# IR_CONTROLLER.net
KiCad netlist of a schematic drawn in Altium Designer
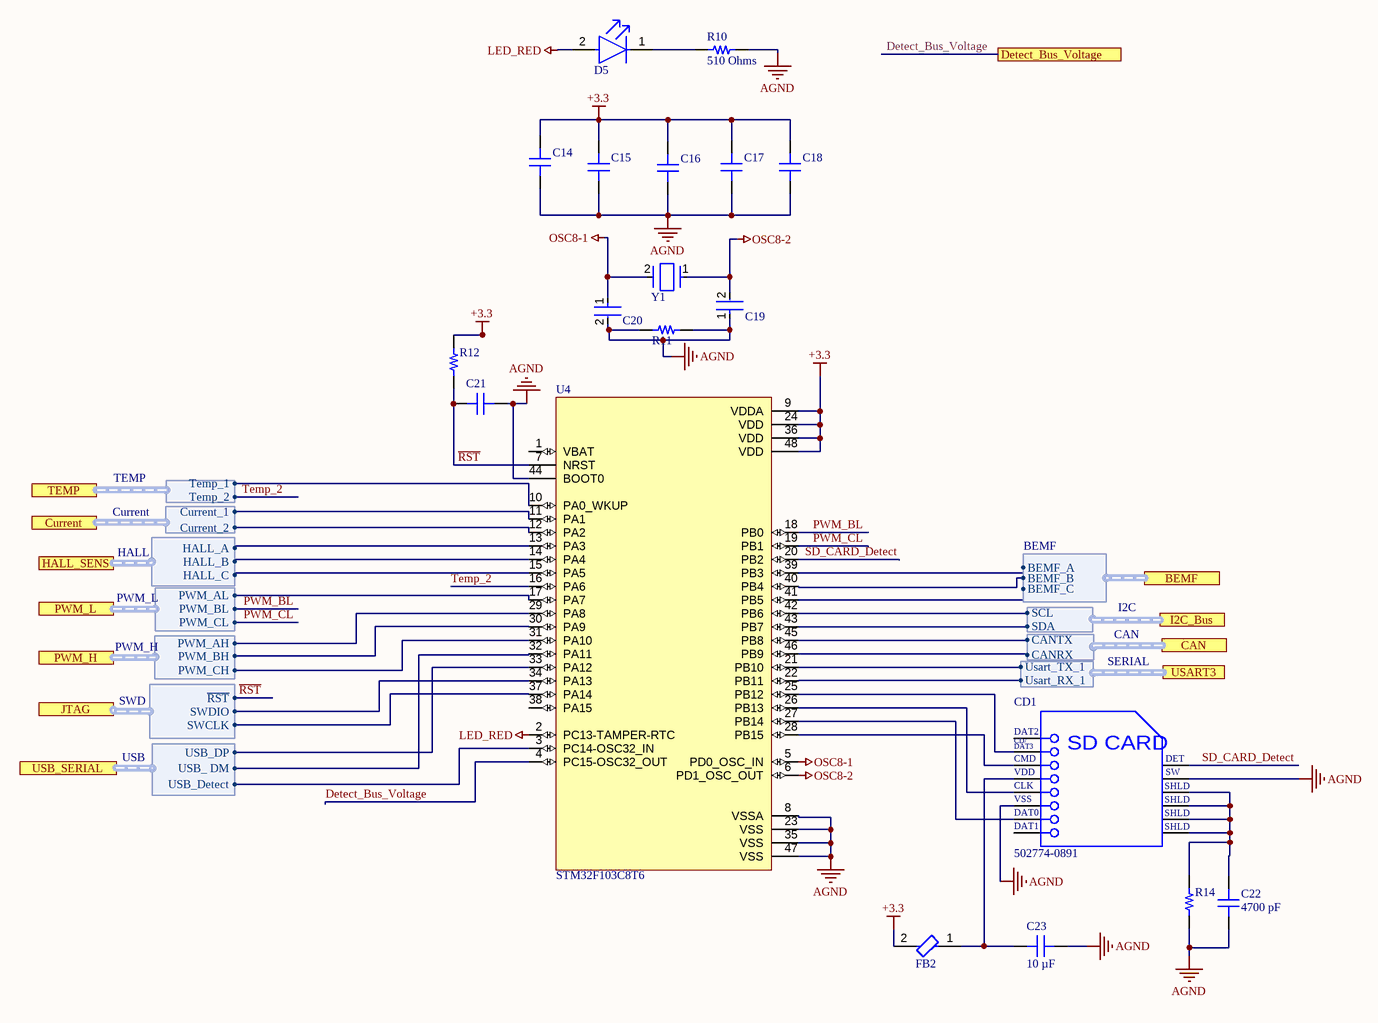
[diagram p0: IR_CONTROLLER.SchDoc]

(export (version "E")
  (design (tool "Eeschema 10.0.6"))
  (components
    (comp (ref "C14")
      (value "0.1 µF")
      (footprint "CAP 0603_1608")
      (description "CAP CER 0.1UF 16V X7R 0603")
      (fields (field (name "PART NUMBER") "CS0603KRX7R7BB104"))
      (libsource (lib "Celestial Altium Library - altium_library") (part "Capacitor"))
    )
    (comp (ref "C15")
      (value "0.1 µF")
      (footprint "CAP 0603_1608")
      (description "CAP CER 0.1UF 16V X7R 0603")
      (fields (field (name "PART NUMBER") "CS0603KRX7R7BB104"))
      (libsource (lib "Celestial Altium Library - altium_library") (part "Capacitor"))
    )
    (comp (ref "C16")
      (value "0.1 µF")
      (footprint "CAP 0603_1608")
      (description "CAP CER 0.1UF 16V X7R 0603")
      (fields (field (name "PART NUMBER") "CS0603KRX7R7BB104"))
      (libsource (lib "Celestial Altium Library - altium_library") (part "Capacitor"))
    )
    (comp (ref "C17")
      (value "0.1 µF")
      (footprint "CAP 0603_1608")
      (description "CAP CER 0.1UF 16V X7R 0603")
      (fields (field (name "PART NUMBER") "CS0603KRX7R7BB104"))
      (libsource (lib "Celestial Altium Library - altium_library") (part "Capacitor"))
    )
    (comp (ref "C18")
      (value "10 µF")
      (footprint "CAP 0603_1608")
      (description "CAP CER 10UF 2.5V X6S 0603")
      (fields (field (name "PART NUMBER") "GRM188C80E106ME47D"))
      (libsource (lib "Celestial Altium Library - altium_library") (part "Capacitor"))
    )
    (comp (ref "C19")
      (value "10pF")
      (footprint "FP-C0805C-DN-MFG")
      (description "Capacitor; Ceramic; Cap 10 pF; Tol 5%; Vol-Rtg 50 VDC; SMT; 0805; COG (NPO); Tape&Reel")
      (fields
        (field (name "OCTOPART") "https://octopart.com/c0805c100j5gactu-kemet-104357")
        (field (name "MANUFACTURER PART NUMBER") "C0805C100J5GACTU")
      )
      (libsource (lib "Altium Content Vault") (part "b4654b650e69147ec39a6b967a45e02"))
    )
    (comp (ref "C20")
      (value "10pF")
      (footprint "FP-C0805C-DN-MFG")
      (description "Capacitor; Ceramic; Cap 10 pF; Tol 5%; Vol-Rtg 50 VDC; SMT; 0805; COG (NPO); Tape&Reel")
      (fields
        (field (name "OCTOPART") "https://octopart.com/c0805c100j5gactu-kemet-104357")
        (field (name "MANUFACTURER PART NUMBER") "C0805C100J5GACTU")
      )
      (libsource (lib "Altium Content Vault") (part "b4654b650e69147ec39a6b967a45e02"))
    )
    (comp (ref "C21")
      (value "100 nF")
      (footprint "CAP 0603_1608")
      (description "CAP CER 10UF 2.5V X6S 0603")
      (fields (field (name "PART NUMBER") "GRM188C80E106ME47D"))
      (libsource (lib "Celestial Altium Library - altium_library") (part "Capacitor"))
    )
    (comp (ref "C22")
      (value "4700 pF")
      (footprint "CAP 0805_2012")
      (description "CAP CER 4700PF 50V X7R 0805")
      (fields (field (name "PART NUMBER") "C0805C472K5RACAUTO") (field (name "MANUFACTURER") "KEMET"))
      (libsource (lib "Celestial Altium Library - altium_library") (part "Capacitor"))
    )
    (comp (ref "C23")
      (value "10 µF")
      (footprint "CAP 0603_1608")
      (description "CAP CER 10UF 6.3V X5R 0603")
      (fields
        (field (name "PART NUMBER") "GRM188R60J106ME47D")
        (field (name "MANUFACTURER") "Murata Electronics")
      )
      (libsource (lib "Celestial Altium Library - altium_library") (part "Capacitor"))
    )
    (comp (ref "CD1")
      (value "502774-0891")
      (footprint "MOLX-502774-0891_V")
      (description "Micro SD Memory Card Connector, 0.5 A, 10 V (DC), -25 to 85 degC, 8-Pin SMT, RoHS, Tape and Reel")
      (fields (field (name "MANUFACTURER") "Molex"))
      (libsource (lib "Altium Content Vault") (part "CN-SD-8-2SW-4S_B"))
    )
    (comp (ref "D5")
      (value "CMD15-21VRD/TR8")
      (footprint "FP-CMD15-21-MFG")
      (description "LED RED DIFFUSED 1206 SMD")
      (fields
        (field (name "MANUFACTURER") "VCC")
        (field (name "OCTOPART") "https://octopart.com/cmd15-21vrd%2Ftr8-vcc-26668835")
      )
      (libsource (lib "Altium Content Vault") (part "8706943c75ba83719d021d2fdc84c58"))
    )
    (comp (ref "FB2")
      (value "BLM18PG330SN1D")
      (footprint "FP-BLM18-0_15-t0_8-d1_2-MFG")
      (description "Chip Ferrite Bead, 0603, 33Ω @ 100MHz, 0.025Ω, 25%, 3A")
      (fields (field (name "TOLERANCE") "25%"))
      (libsource (lib "Altium Content Vault") (part "5f30dd21d616792df468990f7003faa"))
    )
    (comp (ref "R10")
      (value "510 Ohms")
      (footprint "RES 0603_1608")
      (description "RES 10K OHM 0.1% 1/16W 0603")
      (fields
        (field (name "PART NUMBER") "RNCS0603BKE10K0")
        (field (name "MANUFACTURER") "Stackpole Electronics Inc")
      )
      (libsource (lib "Celestial Altium Library - altium_library") (part "Resistor"))
    )
    (comp (ref "R11")
      (value "1M Ohms")
      (footprint "RES 0603_1608")
      (description "RES 10K OHM 0.1% 1/16W 0603")
      (fields
        (field (name "PART NUMBER") "RNCS0603BKE10K0")
        (field (name "MANUFACTURER") "Stackpole Electronics Inc")
      )
      (libsource (lib "Celestial Altium Library - altium_library") (part "Resistor"))
    )
    (comp (ref "R12")
      (value "4.7 kOhms")
      (footprint "RES 0603_1608")
      (description "RES SMD 4.7K OHM 0.1% 1/16W 0603")
      (fields
        (field (name "PART NUMBER") "CPF0603B4K7E1")
        (field (name "MANUFACTURER") "TE Connectivity Passive Product")
      )
      (libsource (lib "Celestial Altium Library - altium_library") (part "Resistor"))
    )
    (comp (ref "R14")
      (value "1 MOhms")
      (footprint "RES 0603_1608")
      (description "RES SMD 1M OHM 0.1% 1/10W 0603")
      (fields (field (name "PART NUMBER") "RT0603BRD071ML") (field (name "MANUFACTURER") "Yageo"))
      (libsource (lib "Celestial Altium Library - altium_library") (part "Resistor"))
    )
    (comp (ref "U4")
      (value "STM32F103C8T6")
      (footprint "QFN48-(7mmX7mm)")
      (description "IC MCU 32-Bit 72MHz 64kB FLASH LQFP48")
      (fields (field (name "MF") "STMicroelectronics"))
      (libsource (lib "Altium_Lib") (part "STM32F103C8T6"))
    )
    (comp (ref "Y1")
      (value "ABM3-8.000MHZ-D2Y-T")
      (footprint "FP-ABM3-MFG")
      (description "Crystal 8MHz ±20ppm 18pF SMD-2 5mm x 3.2mm")
      (fields (field (name "TOLERANCE") "20ppm"))
      (libsource (lib "Altium Content Vault") (part "c23a69dc6c9e2f18f2079038eb95dd1"))
    )
  )
  (nets
    (net (code "12") (name "+3.3") (class "Default")
      (node (ref "C14") (pin "2") (pinfunction "2_2") (pintype "passive"))
      (node (ref "C15") (pin "2") (pinfunction "2_2") (pintype "passive"))
      (node (ref "C16") (pin "2") (pinfunction "2_2") (pintype "passive"))
      (node (ref "C17") (pin "2") (pinfunction "2_2") (pintype "passive"))
      (node (ref "C18") (pin "2") (pinfunction "2_2") (pintype "passive"))
      (node (ref "FB2") (pin "2") (pinfunction "2_2") (pintype "passive"))
      (node (ref "R12") (pin "2") (pinfunction "2_2") (pintype "passive"))
      (node (ref "U4") (pin "24") (pinfunction "VDD_24") (pintype "passive"))
      (node (ref "U4") (pin "36") (pinfunction "VDD_36") (pintype "passive"))
      (node (ref "U4") (pin "48") (pinfunction "VDD_48") (pintype "passive"))
      (node (ref "U4") (pin "9") (pinfunction "VDDA_9") (pintype "passive"))
    )
    (net (code "13") (name "/BEMF_A") (class "Default")
      (node (ref "U4") (pin "39") (pinfunction "PB3_39") (pintype "bidirectional"))
    )
    (net (code "14") (name "/BEMF_B") (class "Default")
      (node (ref "U4") (pin "40") (pinfunction "PB4_40") (pintype "bidirectional"))
    )
    (net (code "15") (name "/BEMF_C") (class "Default")
      (node (ref "U4") (pin "41") (pinfunction "PB5_41") (pintype "bidirectional"))
    )
    (net (code "16") (name "/CANRX") (class "Default")
      (node (ref "U4") (pin "46") (pinfunction "PB9_46") (pintype "bidirectional"))
    )
    (net (code "17") (name "/CANTX") (class "Default")
      (node (ref "U4") (pin "45") (pinfunction "PB8_45") (pintype "bidirectional"))
    )
    (net (code "18") (name "/Current_1") (class "Default")
      (node (ref "U4") (pin "11") (pinfunction "PA1_11") (pintype "bidirectional"))
    )
    (net (code "19") (name "/Current_2") (class "Default")
      (node (ref "U4") (pin "12") (pinfunction "PA2_12") (pintype "bidirectional"))
    )
    (net (code "20") (name "/Detect_Bus_Voltage") (class "Default")
      (node (ref "U4") (pin "4") (pinfunction "PC15-OSC32_OUT_4") (pintype "bidirectional"))
    )
    (net (code "21") (name "/HALL_A") (class "Default")
      (node (ref "U4") (pin "13") (pinfunction "PA3_13") (pintype "bidirectional"))
    )
    (net (code "22") (name "/HALL_B") (class "Default")
      (node (ref "U4") (pin "14") (pinfunction "PA4_14") (pintype "bidirectional"))
    )
    (net (code "23") (name "/HALL_C") (class "Default")
      (node (ref "U4") (pin "15") (pinfunction "PA5_15") (pintype "bidirectional"))
    )
    (net (code "24") (name "/PWM_AH") (class "Default")
      (node (ref "U4") (pin "29") (pinfunction "PA8_29") (pintype "bidirectional"))
    )
    (net (code "25") (name "/PWM_AL") (class "Default")
      (node (ref "U4") (pin "17") (pinfunction "PA7_17") (pintype "bidirectional"))
    )
    (net (code "26") (name "/PWM_BH") (class "Default")
      (node (ref "U4") (pin "30") (pinfunction "PA9_30") (pintype "bidirectional"))
    )
    (net (code "27") (name "/PWM_BL") (class "Default")
      (node (ref "U4") (pin "18") (pinfunction "PB0_18") (pintype "bidirectional"))
    )
    (net (code "28") (name "/PWM_CH") (class "Default")
      (node (ref "U4") (pin "31") (pinfunction "PA10_31") (pintype "bidirectional"))
    )
    (net (code "29") (name "/PWM_CL") (class "Default")
      (node (ref "U4") (pin "19") (pinfunction "PB1_19") (pintype "bidirectional"))
    )
    (net (code "31") (name "/SCL") (class "Default")
      (node (ref "U4") (pin "42") (pinfunction "PB6_42") (pintype "bidirectional"))
    )
    (net (code "32") (name "/SDA") (class "Default")
      (node (ref "U4") (pin "43") (pinfunction "PB7_43") (pintype "bidirectional"))
    )
    (net (code "33") (name "/SD_CARD_Detect") (class "Default")
      (node (ref "CD1") (pin "9") (pinfunction "DETECT_9") (pintype "passive"))
      (node (ref "U4") (pin "20") (pinfunction "PB2_20") (pintype "bidirectional"))
    )
    (net (code "34") (name "/SWCLK") (class "Default")
      (node (ref "U4") (pin "37") (pinfunction "PA14_37") (pintype "bidirectional"))
    )
    (net (code "35") (name "/SWDIO") (class "Default")
      (node (ref "U4") (pin "34") (pinfunction "PA13_34") (pintype "bidirectional"))
    )
    (net (code "36") (name "/Temp_1") (class "Default")
      (node (ref "U4") (pin "10") (pinfunction "PA0_WKUP_10") (pintype "bidirectional"))
    )
    (net (code "37") (name "/Temp_2") (class "Default")
      (node (ref "U4") (pin "16") (pinfunction "PA6_16") (pintype "bidirectional"))
    )
    (net (code "38") (name "/USB_ DM") (class "Default")
      (node (ref "U4") (pin "32") (pinfunction "PA11_32") (pintype "bidirectional"))
    )
    (net (code "39") (name "/USB_DP") (class "Default")
      (node (ref "U4") (pin "33") (pinfunction "PA12_33") (pintype "bidirectional"))
    )
    (net (code "40") (name "/USB_Detect") (class "Default")
      (node (ref "U4") (pin "3") (pinfunction "PC14-OSC32_IN_3") (pintype "bidirectional"))
    )
    (net (code "41") (name "/Usart_RX_1") (class "Default")
      (node (ref "U4") (pin "22") (pinfunction "PB11_22") (pintype "bidirectional"))
    )
    (net (code "42") (name "/Usart_TX_1") (class "Default")
      (node (ref "U4") (pin "21") (pinfunction "PB10_21") (pintype "bidirectional"))
    )
    (net (code "53") (name "/~{RST}") (class "Default")
      (node (ref "C21") (pin "2") (pinfunction "2_2") (pintype "passive"))
      (node (ref "R12") (pin "1") (pinfunction "1_1") (pintype "passive"))
      (node (ref "U4") (pin "7") (pinfunction "NRST_7") (pintype "passive"))
    )
    (net (code "54") (name "AGND") (class "Default")
      (node (ref "C14") (pin "1") (pinfunction "1_1") (pintype "passive"))
      (node (ref "C15") (pin "1") (pinfunction "1_1") (pintype "passive"))
      (node (ref "C16") (pin "1") (pinfunction "1_1") (pintype "passive"))
      (node (ref "C17") (pin "1") (pinfunction "1_1") (pintype "passive"))
      (node (ref "C18") (pin "1") (pinfunction "1_1") (pintype "passive"))
      (node (ref "C19") (pin "1") (pinfunction "1_1") (pintype "passive"))
      (node (ref "C20") (pin "2") (pinfunction "2_2") (pintype "passive"))
      (node (ref "C21") (pin "1") (pinfunction "1_1") (pintype "passive"))
      (node (ref "C22") (pin "1") (pinfunction "1_1") (pintype "passive"))
      (node (ref "C23") (pin "2") (pinfunction "2_2") (pintype "passive"))
      (node (ref "CD1") (pin "10") (pinfunction "SWITCH_10") (pintype "passive"))
      (node (ref "CD1") (pin "6") (pinfunction "VSS_6") (pintype "passive"))
      (node (ref "R10") (pin "2") (pinfunction "2_2") (pintype "passive"))
      (node (ref "R11") (pin "1") (pinfunction "1_1") (pintype "passive"))
      (node (ref "R11") (pin "2") (pinfunction "2_2") (pintype "passive"))
      (node (ref "R14") (pin "1") (pinfunction "1_1") (pintype "passive"))
      (node (ref "U4") (pin "23") (pinfunction "VSS_23") (pintype "passive"))
      (node (ref "U4") (pin "35") (pinfunction "VSS_35") (pintype "passive"))
      (node (ref "U4") (pin "44") (pinfunction "BOOT0_44") (pintype "passive"))
      (node (ref "U4") (pin "47") (pinfunction "VSS_47") (pintype "passive"))
      (node (ref "U4") (pin "8") (pinfunction "VSSA_8") (pintype "passive"))
    )
    (net (code "55") (name "LED_RED") (class "Default")
      (node (ref "D5") (pin "2") (pinfunction "A_2") (pintype "passive"))
      (node (ref "U4") (pin "2") (pinfunction "PC13-TAMPER-RTC_2") (pintype "bidirectional"))
    )
    (net (code "56") (name "Net-(C22-Pad2)") (class "Default")
      (node (ref "C22") (pin "2") (pinfunction "2_2") (pintype "passive"))
      (node (ref "CD1") (pin "11") (pinfunction "SHLD_11") (pintype "passive"))
      (node (ref "CD1") (pin "12") (pinfunction "SHLD_12") (pintype "passive"))
      (node (ref "CD1") (pin "13") (pinfunction "SHLD_13") (pintype "passive"))
      (node (ref "CD1") (pin "14") (pinfunction "SHLD_14") (pintype "passive"))
      (node (ref "R14") (pin "2") (pinfunction "2_2") (pintype "passive"))
    )
    (net (code "57") (name "Net-(CD1-CD{slash}DAT3)") (class "Default")
      (node (ref "CD1") (pin "2") (pinfunction "CD/DAT3_2") (pintype "passive"))
      (node (ref "U4") (pin "25") (pinfunction "PB12_25") (pintype "bidirectional"))
    )
    (net (code "58") (name "Net-(CD1-CLK)") (class "Default")
      (node (ref "CD1") (pin "5") (pinfunction "CLK_5") (pintype "passive"))
      (node (ref "U4") (pin "26") (pinfunction "PB13_26") (pintype "bidirectional"))
    )
    (net (code "59") (name "Net-(CD1-CMD)") (class "Default")
      (node (ref "CD1") (pin "3") (pinfunction "CMD_3") (pintype "passive"))
      (node (ref "U4") (pin "28") (pinfunction "PB15_28") (pintype "bidirectional"))
    )
    (net (code "60") (name "Net-(CD1-DAT0)") (class "Default")
      (node (ref "CD1") (pin "7") (pinfunction "DAT0_7") (pintype "passive"))
      (node (ref "U4") (pin "27") (pinfunction "PB14_27") (pintype "bidirectional"))
    )
    (net (code "61") (name "Net-(CD1-VDD)") (class "Default")
      (node (ref "C23") (pin "1") (pinfunction "1_1") (pintype "passive"))
      (node (ref "CD1") (pin "4") (pinfunction "VDD_4") (pintype "passive"))
      (node (ref "FB2") (pin "1") (pinfunction "1_1") (pintype "passive"))
    )
    (net (code "62") (name "Net-(D5-C)") (class "Default")
      (node (ref "D5") (pin "1") (pinfunction "C_1") (pintype "passive"))
      (node (ref "R10") (pin "1") (pinfunction "1_1") (pintype "passive"))
    )
    (net (code "63") (name "OSC8-1") (class "Default")
      (node (ref "C20") (pin "1") (pinfunction "1_1") (pintype "passive"))
      (node (ref "U4") (pin "5") (pinfunction "PD0_OSC_IN_5") (pintype "bidirectional"))
      (node (ref "Y1") (pin "2") (pinfunction "2_2") (pintype "passive"))
    )
    (net (code "64") (name "OSC8-2") (class "Default")
      (node (ref "C19") (pin "2") (pinfunction "2_2") (pintype "passive"))
      (node (ref "U4") (pin "6") (pinfunction "PD1_OSC_OUT_6") (pintype "bidirectional"))
      (node (ref "Y1") (pin "1") (pinfunction "1_1") (pintype "passive"))
    )
    (net (code "65") (name "unconnected-(CD1-DAT1-Pad8)") (class "Default")
      (node (ref "CD1") (pin "8") (pinfunction "DAT1_8") (pintype "passive"))
    )
    (net (code "66") (name "unconnected-(CD1-DAT2-Pad1)") (class "Default")
      (node (ref "CD1") (pin "1") (pinfunction "DAT2_1") (pintype "passive"))
    )
    (net (code "67") (name "unconnected-(U4-PA15-Pad38)") (class "Default")
      (node (ref "U4") (pin "38") (pinfunction "PA15_38") (pintype "bidirectional"))
    )
    (net (code "68") (name "unconnected-(U4-VBAT-Pad1)") (class "Default")
      (node (ref "U4") (pin "1") (pinfunction "VBAT_1") (pintype "bidirectional"))
    )
  )
)
